# atmega_embedded_main_-_za_drugog_Marka.net
KiCad netlist of a schematic drawn in EAGLE
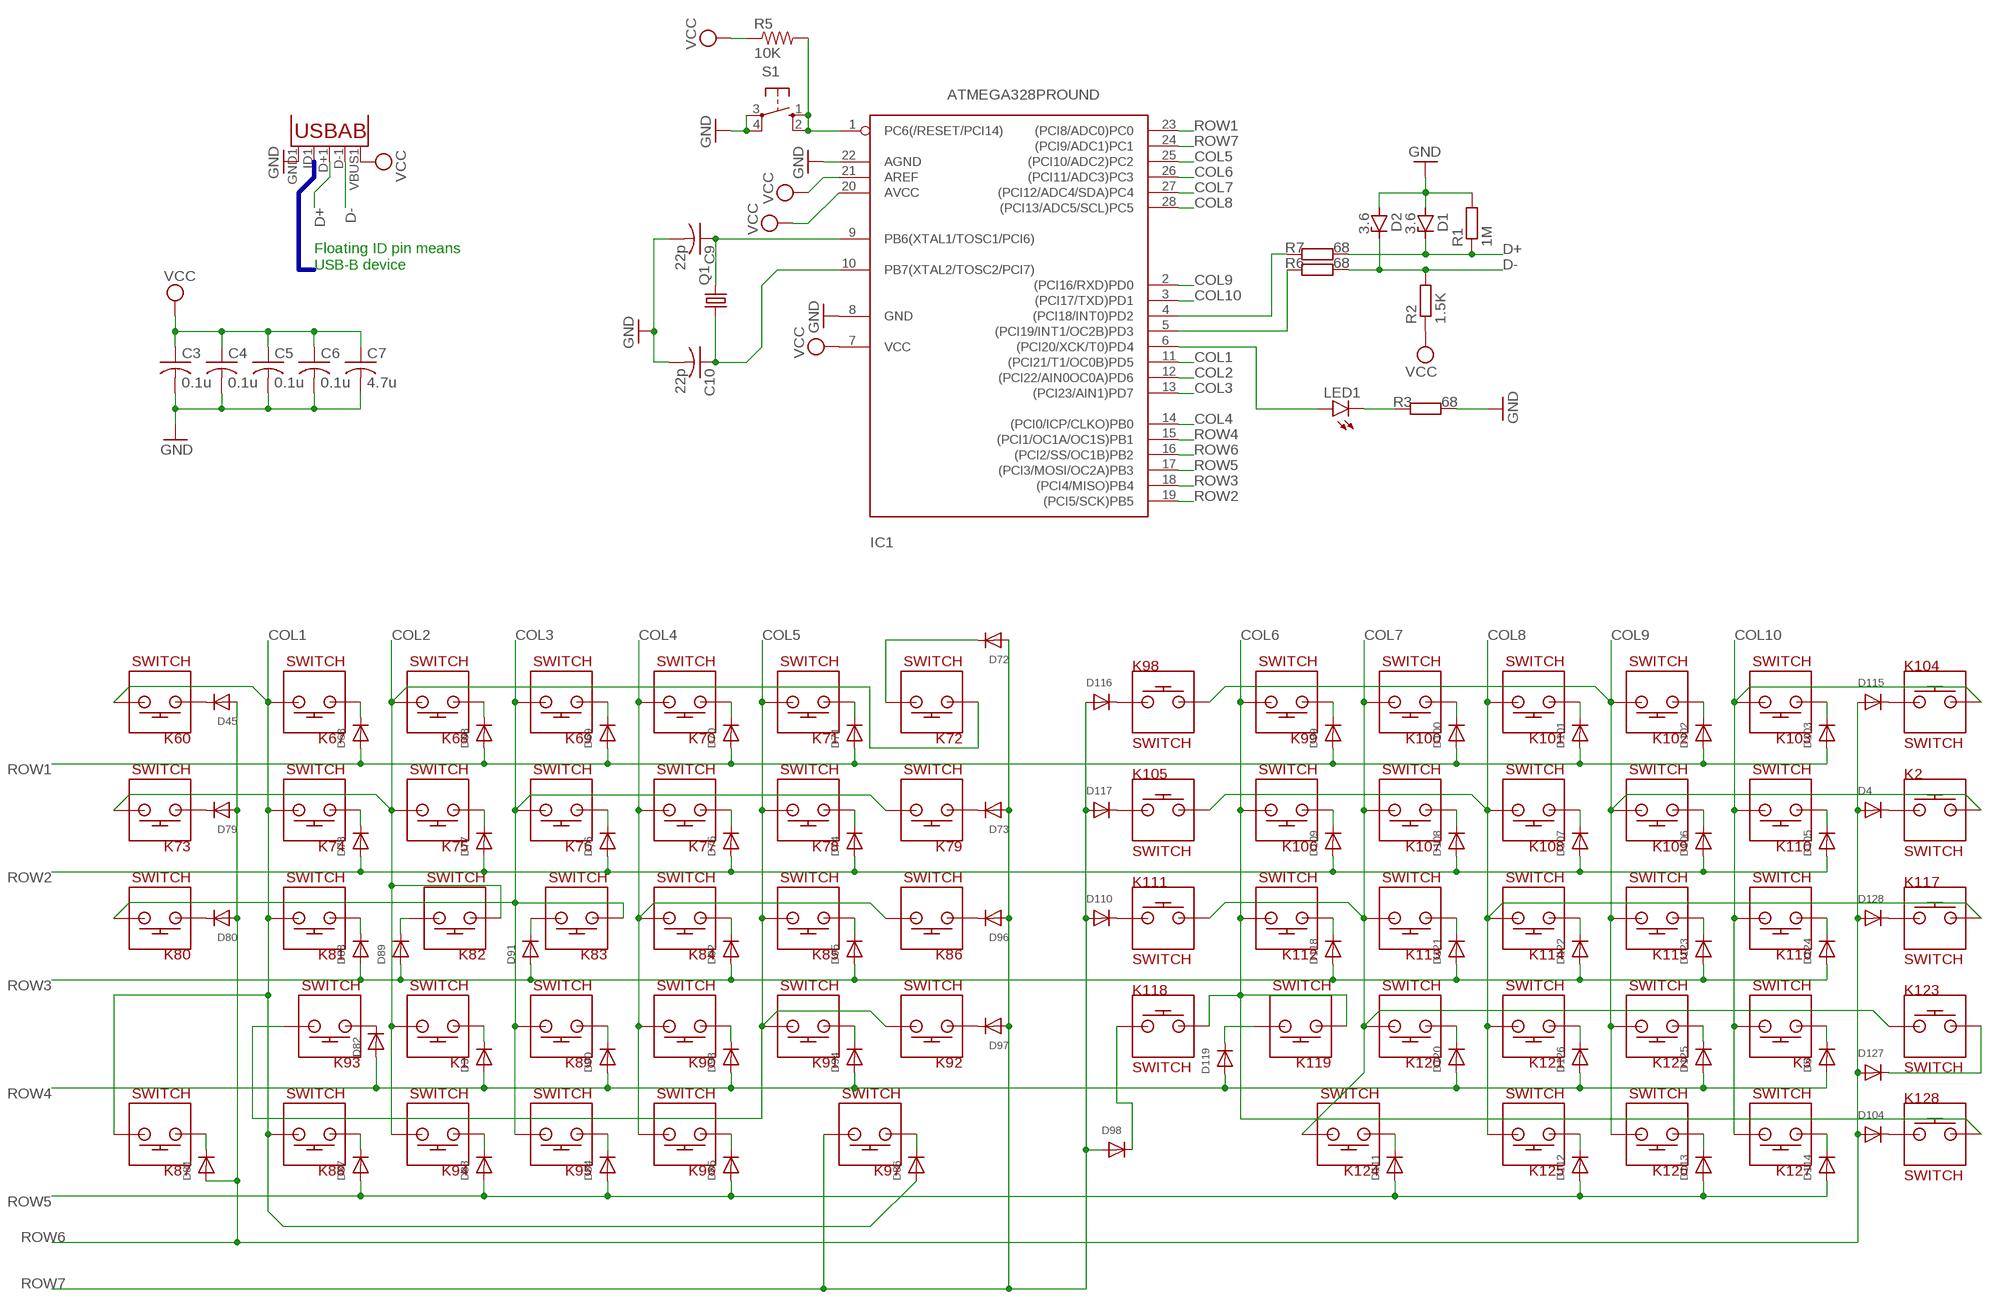
[diagram p0: schematic, sheet 1]

(export (version "E")
  (design (tool "Eeschema 10.0.6"))
  (components
    (comp (ref "C3")
      (value "0.1u")
      (footprint "eagle-import:C0805")
      (libsource (lib "eagle-import") (part "C-USC0805"))
    )
    (comp (ref "C4")
      (value "0.1u")
      (footprint "eagle-import:C0805")
      (libsource (lib "eagle-import") (part "C-USC0805"))
    )
    (comp (ref "C5")
      (value "0.1u")
      (footprint "eagle-import:C0805")
      (libsource (lib "eagle-import") (part "C-USC0805"))
    )
    (comp (ref "C6")
      (value "0.1u")
      (footprint "eagle-import:C0805")
      (libsource (lib "eagle-import") (part "C-USC0805"))
    )
    (comp (ref "C7")
      (value "4.7u")
      (footprint "eagle-import:C0805")
      (libsource (lib "eagle-import") (part "C-USC0805"))
    )
    (comp (ref "C9")
      (value "22p")
      (footprint "eagle-import:C0805")
      (libsource (lib "eagle-import") (part "C-USC0805"))
    )
    (comp (ref "C10")
      (value "22p")
      (footprint "eagle-import:C0805")
      (libsource (lib "eagle-import") (part "C-USC0805"))
    )
    (comp (ref "D1")
      (value "3.6")
      (footprint "eagle-import:SMB")
      (libsource (lib "eagle-import") (part "ZENER-DIODESMB"))
    )
    (comp (ref "D2")
      (value "3.6")
      (footprint "eagle-import:SMB")
      (libsource (lib "eagle-import") (part "ZENER-DIODESMB"))
    )
    (comp (ref "D3")
      (value "DIODESMA")
      (footprint "eagle-import:SMADIODE")
      (libsource (lib "eagle-import") (part "DIODESMA"))
    )
    (comp (ref "D4")
      (value "DIODESMA")
      (footprint "eagle-import:SMADIODE")
      (libsource (lib "eagle-import") (part "DIODESMA"))
    )
    (comp (ref "D5")
      (value "DIODESMA")
      (footprint "eagle-import:SMADIODE")
      (libsource (lib "eagle-import") (part "DIODESMA"))
    )
    (comp (ref "D45")
      (value "DIODESMA")
      (footprint "eagle-import:SMADIODE")
      (libsource (lib "eagle-import") (part "DIODESMA"))
    )
    (comp (ref "D63")
      (value "DIODESMA")
      (footprint "eagle-import:SMADIODE")
      (libsource (lib "eagle-import") (part "DIODESMA"))
    )
    (comp (ref "D68")
      (value "DIODESMA")
      (footprint "eagle-import:SMADIODE")
      (libsource (lib "eagle-import") (part "DIODESMA"))
    )
    (comp (ref "D69")
      (value "DIODESMA")
      (footprint "eagle-import:SMADIODE")
      (libsource (lib "eagle-import") (part "DIODESMA"))
    )
    (comp (ref "D70")
      (value "DIODESMA")
      (footprint "eagle-import:SMADIODE")
      (libsource (lib "eagle-import") (part "DIODESMA"))
    )
    (comp (ref "D71")
      (value "DIODESMA")
      (footprint "eagle-import:SMADIODE")
      (libsource (lib "eagle-import") (part "DIODESMA"))
    )
    (comp (ref "D72")
      (value "DIODESMA")
      (footprint "eagle-import:SMADIODE")
      (libsource (lib "eagle-import") (part "DIODESMA"))
    )
    (comp (ref "D73")
      (value "DIODESMA")
      (footprint "eagle-import:SMADIODE")
      (libsource (lib "eagle-import") (part "DIODESMA"))
    )
    (comp (ref "D74")
      (value "DIODESMA")
      (footprint "eagle-import:SMADIODE")
      (libsource (lib "eagle-import") (part "DIODESMA"))
    )
    (comp (ref "D75")
      (value "DIODESMA")
      (footprint "eagle-import:SMADIODE")
      (libsource (lib "eagle-import") (part "DIODESMA"))
    )
    (comp (ref "D76")
      (value "DIODESMA")
      (footprint "eagle-import:SMADIODE")
      (libsource (lib "eagle-import") (part "DIODESMA"))
    )
    (comp (ref "D77")
      (value "DIODESMA")
      (footprint "eagle-import:SMADIODE")
      (libsource (lib "eagle-import") (part "DIODESMA"))
    )
    (comp (ref "D78")
      (value "DIODESMA")
      (footprint "eagle-import:SMADIODE")
      (libsource (lib "eagle-import") (part "DIODESMA"))
    )
    (comp (ref "D79")
      (value "DIODESMA")
      (footprint "eagle-import:SMADIODE")
      (libsource (lib "eagle-import") (part "DIODESMA"))
    )
    (comp (ref "D80")
      (value "DIODESMA")
      (footprint "eagle-import:SMADIODE")
      (libsource (lib "eagle-import") (part "DIODESMA"))
    )
    (comp (ref "D81")
      (value "DIODESMA")
      (footprint "eagle-import:SMADIODE")
      (libsource (lib "eagle-import") (part "DIODESMA"))
    )
    (comp (ref "D82")
      (value "DIODESMA")
      (footprint "eagle-import:SMADIODE")
      (libsource (lib "eagle-import") (part "DIODESMA"))
    )
    (comp (ref "D83")
      (value "DIODESMA")
      (footprint "eagle-import:SMADIODE")
      (libsource (lib "eagle-import") (part "DIODESMA"))
    )
    (comp (ref "D84")
      (value "DIODESMA")
      (footprint "eagle-import:SMADIODE")
      (libsource (lib "eagle-import") (part "DIODESMA"))
    )
    (comp (ref "D85")
      (value "DIODESMA")
      (footprint "eagle-import:SMADIODE")
      (libsource (lib "eagle-import") (part "DIODESMA"))
    )
    (comp (ref "D86")
      (value "DIODESMA")
      (footprint "eagle-import:SMADIODE")
      (libsource (lib "eagle-import") (part "DIODESMA"))
    )
    (comp (ref "D87")
      (value "DIODESMA")
      (footprint "eagle-import:SMADIODE")
      (libsource (lib "eagle-import") (part "DIODESMA"))
    )
    (comp (ref "D88")
      (value "DIODESMA")
      (footprint "eagle-import:SMADIODE")
      (libsource (lib "eagle-import") (part "DIODESMA"))
    )
    (comp (ref "D89")
      (value "DIODESMA")
      (footprint "eagle-import:SMADIODE")
      (libsource (lib "eagle-import") (part "DIODESMA"))
    )
    (comp (ref "D90")
      (value "DIODESMA")
      (footprint "eagle-import:SMADIODE")
      (libsource (lib "eagle-import") (part "DIODESMA"))
    )
    (comp (ref "D91")
      (value "DIODESMA")
      (footprint "eagle-import:SMADIODE")
      (libsource (lib "eagle-import") (part "DIODESMA"))
    )
    (comp (ref "D92")
      (value "DIODESMA")
      (footprint "eagle-import:SMADIODE")
      (libsource (lib "eagle-import") (part "DIODESMA"))
    )
    (comp (ref "D93")
      (value "DIODESMA")
      (footprint "eagle-import:SMADIODE")
      (libsource (lib "eagle-import") (part "DIODESMA"))
    )
    (comp (ref "D94")
      (value "DIODESMA")
      (footprint "eagle-import:SMADIODE")
      (libsource (lib "eagle-import") (part "DIODESMA"))
    )
    (comp (ref "D95")
      (value "DIODESMA")
      (footprint "eagle-import:SMADIODE")
      (libsource (lib "eagle-import") (part "DIODESMA"))
    )
    (comp (ref "D96")
      (value "DIODESMA")
      (footprint "eagle-import:SMADIODE")
      (libsource (lib "eagle-import") (part "DIODESMA"))
    )
    (comp (ref "D97")
      (value "DIODESMA")
      (footprint "eagle-import:SMADIODE")
      (libsource (lib "eagle-import") (part "DIODESMA"))
    )
    (comp (ref "D98")
      (value "DIODESMA")
      (footprint "eagle-import:SMADIODE")
      (libsource (lib "eagle-import") (part "DIODESMA"))
    )
    (comp (ref "D99")
      (value "DIODESMA")
      (footprint "eagle-import:SMADIODE")
      (libsource (lib "eagle-import") (part "DIODESMA"))
    )
    (comp (ref "D100")
      (value "DIODESMA")
      (footprint "eagle-import:SMADIODE")
      (libsource (lib "eagle-import") (part "DIODESMA"))
    )
    (comp (ref "D101")
      (value "DIODESMA")
      (footprint "eagle-import:SMADIODE")
      (libsource (lib "eagle-import") (part "DIODESMA"))
    )
    (comp (ref "D102")
      (value "DIODESMA")
      (footprint "eagle-import:SMADIODE")
      (libsource (lib "eagle-import") (part "DIODESMA"))
    )
    (comp (ref "D103")
      (value "DIODESMA")
      (footprint "eagle-import:SMADIODE")
      (libsource (lib "eagle-import") (part "DIODESMA"))
    )
    (comp (ref "D104")
      (value "DIODESMA")
      (footprint "eagle-import:SMADIODE")
      (libsource (lib "eagle-import") (part "DIODESMA"))
    )
    (comp (ref "D105")
      (value "DIODESMA")
      (footprint "eagle-import:SMADIODE")
      (libsource (lib "eagle-import") (part "DIODESMA"))
    )
    (comp (ref "D106")
      (value "DIODESMA")
      (footprint "eagle-import:SMADIODE")
      (libsource (lib "eagle-import") (part "DIODESMA"))
    )
    (comp (ref "D107")
      (value "DIODESMA")
      (footprint "eagle-import:SMADIODE")
      (libsource (lib "eagle-import") (part "DIODESMA"))
    )
    (comp (ref "D108")
      (value "DIODESMA")
      (footprint "eagle-import:SMADIODE")
      (libsource (lib "eagle-import") (part "DIODESMA"))
    )
    (comp (ref "D109")
      (value "DIODESMA")
      (footprint "eagle-import:SMADIODE")
      (libsource (lib "eagle-import") (part "DIODESMA"))
    )
    (comp (ref "D110")
      (value "DIODESMA")
      (footprint "eagle-import:SMADIODE")
      (libsource (lib "eagle-import") (part "DIODESMA"))
    )
    (comp (ref "D111")
      (value "DIODESMA")
      (footprint "eagle-import:SMADIODE")
      (libsource (lib "eagle-import") (part "DIODESMA"))
    )
    (comp (ref "D112")
      (value "DIODESMA")
      (footprint "eagle-import:SMADIODE")
      (libsource (lib "eagle-import") (part "DIODESMA"))
    )
    (comp (ref "D113")
      (value "DIODESMA")
      (footprint "eagle-import:SMADIODE")
      (libsource (lib "eagle-import") (part "DIODESMA"))
    )
    (comp (ref "D114")
      (value "DIODESMA")
      (footprint "eagle-import:SMADIODE")
      (libsource (lib "eagle-import") (part "DIODESMA"))
    )
    (comp (ref "D115")
      (value "DIODESMA")
      (footprint "eagle-import:SMADIODE")
      (libsource (lib "eagle-import") (part "DIODESMA"))
    )
    (comp (ref "D116")
      (value "DIODESMA")
      (footprint "eagle-import:SMADIODE")
      (libsource (lib "eagle-import") (part "DIODESMA"))
    )
    (comp (ref "D117")
      (value "DIODESMA")
      (footprint "eagle-import:SMADIODE")
      (libsource (lib "eagle-import") (part "DIODESMA"))
    )
    (comp (ref "D118")
      (value "DIODESMA")
      (footprint "eagle-import:SMADIODE")
      (libsource (lib "eagle-import") (part "DIODESMA"))
    )
    (comp (ref "D119")
      (value "DIODESMA")
      (footprint "eagle-import:SMADIODE")
      (libsource (lib "eagle-import") (part "DIODESMA"))
    )
    (comp (ref "D120")
      (value "DIODESMA")
      (footprint "eagle-import:SMADIODE")
      (libsource (lib "eagle-import") (part "DIODESMA"))
    )
    (comp (ref "D121")
      (value "DIODESMA")
      (footprint "eagle-import:SMADIODE")
      (libsource (lib "eagle-import") (part "DIODESMA"))
    )
    (comp (ref "D122")
      (value "DIODESMA")
      (footprint "eagle-import:SMADIODE")
      (libsource (lib "eagle-import") (part "DIODESMA"))
    )
    (comp (ref "D123")
      (value "DIODESMA")
      (footprint "eagle-import:SMADIODE")
      (libsource (lib "eagle-import") (part "DIODESMA"))
    )
    (comp (ref "D124")
      (value "DIODESMA")
      (footprint "eagle-import:SMADIODE")
      (libsource (lib "eagle-import") (part "DIODESMA"))
    )
    (comp (ref "D125")
      (value "DIODESMA")
      (footprint "eagle-import:SMADIODE")
      (libsource (lib "eagle-import") (part "DIODESMA"))
    )
    (comp (ref "D126")
      (value "DIODESMA")
      (footprint "eagle-import:SMADIODE")
      (libsource (lib "eagle-import") (part "DIODESMA"))
    )
    (comp (ref "D127")
      (value "DIODESMA")
      (footprint "eagle-import:SMADIODE")
      (libsource (lib "eagle-import") (part "DIODESMA"))
    )
    (comp (ref "D128")
      (value "DIODESMA")
      (footprint "eagle-import:SMADIODE")
      (libsource (lib "eagle-import") (part "DIODESMA"))
    )
    (comp (ref "IC1")
      (value "ATMEGA328PROUND")
      (footprint "eagle-import:DIL28-3-ROUND")
      (libsource (lib "eagle-import") (part "ATMEGA328PROUND"))
    )
    (comp (ref "K1")
      (value "SWITCH")
      (footprint "eagle-import:KAILH_LOW_PROFILE")
      (libsource (lib "eagle-import") (part "SWITCH"))
    )
    (comp (ref "K2")
      (value "SWITCH")
      (footprint "eagle-import:KAILH_LOW_PROFILE")
      (libsource (lib "eagle-import") (part "SWITCH"))
    )
    (comp (ref "K3")
      (value "SWITCH")
      (footprint "eagle-import:KAILH_LOW_PROFILE")
      (libsource (lib "eagle-import") (part "SWITCH"))
    )
    (comp (ref "K60")
      (value "SWITCH")
      (footprint "eagle-import:KAILH_LOW_PROFILE")
      (libsource (lib "eagle-import") (part "SWITCH"))
    )
    (comp (ref "K67")
      (value "SWITCH")
      (footprint "eagle-import:KAILH_LOW_PROFILE")
      (libsource (lib "eagle-import") (part "SWITCH"))
    )
    (comp (ref "K68")
      (value "SWITCH")
      (footprint "eagle-import:KAILH_LOW_PROFILE")
      (libsource (lib "eagle-import") (part "SWITCH"))
    )
    (comp (ref "K69")
      (value "SWITCH")
      (footprint "eagle-import:KAILH_LOW_PROFILE")
      (libsource (lib "eagle-import") (part "SWITCH"))
    )
    (comp (ref "K70")
      (value "SWITCH")
      (footprint "eagle-import:KAILH_LOW_PROFILE")
      (libsource (lib "eagle-import") (part "SWITCH"))
    )
    (comp (ref "K71")
      (value "SWITCH")
      (footprint "eagle-import:KAILH_LOW_PROFILE")
      (libsource (lib "eagle-import") (part "SWITCH"))
    )
    (comp (ref "K72")
      (value "SWITCH")
      (footprint "eagle-import:KAILH_LOW_PROFILE")
      (libsource (lib "eagle-import") (part "SWITCH"))
    )
    (comp (ref "K73")
      (value "SWITCH")
      (footprint "eagle-import:KAILH_LOW_PROFILE")
      (libsource (lib "eagle-import") (part "SWITCH"))
    )
    (comp (ref "K74")
      (value "SWITCH")
      (footprint "eagle-import:KAILH_LOW_PROFILE")
      (libsource (lib "eagle-import") (part "SWITCH"))
    )
    (comp (ref "K75")
      (value "SWITCH")
      (footprint "eagle-import:KAILH_LOW_PROFILE")
      (libsource (lib "eagle-import") (part "SWITCH"))
    )
    (comp (ref "K76")
      (value "SWITCH")
      (footprint "eagle-import:KAILH_LOW_PROFILE")
      (libsource (lib "eagle-import") (part "SWITCH"))
    )
    (comp (ref "K77")
      (value "SWITCH")
      (footprint "eagle-import:KAILH_LOW_PROFILE")
      (libsource (lib "eagle-import") (part "SWITCH"))
    )
    (comp (ref "K78")
      (value "SWITCH")
      (footprint "eagle-import:KAILH_LOW_PROFILE")
      (libsource (lib "eagle-import") (part "SWITCH"))
    )
    (comp (ref "K79")
      (value "SWITCH")
      (footprint "eagle-import:KAILH_LOW_PROFILE")
      (libsource (lib "eagle-import") (part "SWITCH"))
    )
    (comp (ref "K80")
      (value "SWITCH")
      (footprint "eagle-import:KAILH_LOW_PROFILE")
      (libsource (lib "eagle-import") (part "SWITCH"))
    )
    (comp (ref "K81")
      (value "SWITCH")
      (footprint "eagle-import:KAILH_LOW_PROFILE")
      (libsource (lib "eagle-import") (part "SWITCH"))
    )
    (comp (ref "K82")
      (value "SWITCH")
      (footprint "eagle-import:KAILH_LOW_PROFILE")
      (libsource (lib "eagle-import") (part "SWITCH"))
    )
    (comp (ref "K83")
      (value "SWITCH")
      (footprint "eagle-import:KAILH_LOW_PROFILE")
      (libsource (lib "eagle-import") (part "SWITCH"))
    )
    (comp (ref "K84")
      (value "SWITCH")
      (footprint "eagle-import:KAILH_LOW_PROFILE")
      (libsource (lib "eagle-import") (part "SWITCH"))
    )
    (comp (ref "K85")
      (value "SWITCH")
      (footprint "eagle-import:KAILH_LOW_PROFILE")
      (libsource (lib "eagle-import") (part "SWITCH"))
    )
    (comp (ref "K86")
      (value "SWITCH")
      (footprint "eagle-import:KAILH_LOW_PROFILE")
      (libsource (lib "eagle-import") (part "SWITCH"))
    )
    (comp (ref "K87")
      (value "SWITCH")
      (footprint "eagle-import:KAILH_LOW_PROFILE")
      (libsource (lib "eagle-import") (part "SWITCH"))
    )
    (comp (ref "K88")
      (value "SWITCH")
      (footprint "eagle-import:KAILH_LOW_PROFILE")
      (libsource (lib "eagle-import") (part "SWITCH"))
    )
    (comp (ref "K89")
      (value "SWITCH")
      (footprint "eagle-import:KAILH_LOW_PROFILE")
      (libsource (lib "eagle-import") (part "SWITCH"))
    )
    (comp (ref "K90")
      (value "SWITCH")
      (footprint "eagle-import:KAILH_LOW_PROFILE")
      (libsource (lib "eagle-import") (part "SWITCH"))
    )
    (comp (ref "K91")
      (value "SWITCH")
      (footprint "eagle-import:KAILH_LOW_PROFILE")
      (libsource (lib "eagle-import") (part "SWITCH"))
    )
    (comp (ref "K92")
      (value "SWITCH")
      (footprint "eagle-import:KAILH_LOW_PROFILE")
      (libsource (lib "eagle-import") (part "SWITCH"))
    )
    (comp (ref "K93")
      (value "SWITCH")
      (footprint "eagle-import:KAILH_LOW_PROFILE")
      (libsource (lib "eagle-import") (part "SWITCH"))
    )
    (comp (ref "K94")
      (value "SWITCH")
      (footprint "eagle-import:KAILH_LOW_PROFILE")
      (libsource (lib "eagle-import") (part "SWITCH"))
    )
    (comp (ref "K95")
      (value "SWITCH")
      (footprint "eagle-import:KAILH_LOW_PROFILE")
      (libsource (lib "eagle-import") (part "SWITCH"))
    )
    (comp (ref "K96")
      (value "SWITCH")
      (footprint "eagle-import:KAILH_LOW_PROFILE")
      (libsource (lib "eagle-import") (part "SWITCH"))
    )
    (comp (ref "K97")
      (value "SWITCH")
      (footprint "eagle-import:KAILH_LOW_PROFILE")
      (libsource (lib "eagle-import") (part "SWITCH"))
    )
    (comp (ref "K98")
      (value "SWITCH")
      (footprint "eagle-import:KAILH_LOW_PROFILE")
      (libsource (lib "eagle-import") (part "SWITCH"))
    )
    (comp (ref "K99")
      (value "SWITCH")
      (footprint "eagle-import:KAILH_LOW_PROFILE")
      (libsource (lib "eagle-import") (part "SWITCH"))
    )
    (comp (ref "K100")
      (value "SWITCH")
      (footprint "eagle-import:KAILH_LOW_PROFILE")
      (libsource (lib "eagle-import") (part "SWITCH"))
    )
    (comp (ref "K101")
      (value "SWITCH")
      (footprint "eagle-import:KAILH_LOW_PROFILE")
      (libsource (lib "eagle-import") (part "SWITCH"))
    )
    (comp (ref "K102")
      (value "SWITCH")
      (footprint "eagle-import:KAILH_LOW_PROFILE")
      (libsource (lib "eagle-import") (part "SWITCH"))
    )
    (comp (ref "K103")
      (value "SWITCH")
      (footprint "eagle-import:KAILH_LOW_PROFILE")
      (libsource (lib "eagle-import") (part "SWITCH"))
    )
    (comp (ref "K104")
      (value "SWITCH")
      (footprint "eagle-import:KAILH_LOW_PROFILE")
      (libsource (lib "eagle-import") (part "SWITCH"))
    )
    (comp (ref "K105")
      (value "SWITCH")
      (footprint "eagle-import:KAILH_LOW_PROFILE")
      (libsource (lib "eagle-import") (part "SWITCH"))
    )
    (comp (ref "K106")
      (value "SWITCH")
      (footprint "eagle-import:KAILH_LOW_PROFILE")
      (libsource (lib "eagle-import") (part "SWITCH"))
    )
    (comp (ref "K107")
      (value "SWITCH")
      (footprint "eagle-import:KAILH_LOW_PROFILE")
      (libsource (lib "eagle-import") (part "SWITCH"))
    )
    (comp (ref "K108")
      (value "SWITCH")
      (footprint "eagle-import:KAILH_LOW_PROFILE")
      (libsource (lib "eagle-import") (part "SWITCH"))
    )
    (comp (ref "K109")
      (value "SWITCH")
      (footprint "eagle-import:KAILH_LOW_PROFILE")
      (libsource (lib "eagle-import") (part "SWITCH"))
    )
    (comp (ref "K110")
      (value "SWITCH")
      (footprint "eagle-import:KAILH_LOW_PROFILE")
      (libsource (lib "eagle-import") (part "SWITCH"))
    )
    (comp (ref "K111")
      (value "SWITCH")
      (footprint "eagle-import:KAILH_LOW_PROFILE")
      (libsource (lib "eagle-import") (part "SWITCH"))
    )
    (comp (ref "K112")
      (value "SWITCH")
      (footprint "eagle-import:KAILH_LOW_PROFILE")
      (libsource (lib "eagle-import") (part "SWITCH"))
    )
    (comp (ref "K113")
      (value "SWITCH")
      (footprint "eagle-import:KAILH_LOW_PROFILE")
      (libsource (lib "eagle-import") (part "SWITCH"))
    )
    (comp (ref "K114")
      (value "SWITCH")
      (footprint "eagle-import:KAILH_LOW_PROFILE")
      (libsource (lib "eagle-import") (part "SWITCH"))
    )
    (comp (ref "K115")
      (value "SWITCH")
      (footprint "eagle-import:KAILH_LOW_PROFILE")
      (libsource (lib "eagle-import") (part "SWITCH"))
    )
    (comp (ref "K116")
      (value "SWITCH")
      (footprint "eagle-import:KAILH_LOW_PROFILE")
      (libsource (lib "eagle-import") (part "SWITCH"))
    )
    (comp (ref "K117")
      (value "SWITCH")
      (footprint "eagle-import:KAILH_LOW_PROFILE")
      (libsource (lib "eagle-import") (part "SWITCH"))
    )
    (comp (ref "K118")
      (value "SWITCH")
      (footprint "eagle-import:KAILH_LOW_PROFILE")
      (libsource (lib "eagle-import") (part "SWITCH"))
    )
    (comp (ref "K119")
      (value "SWITCH")
      (footprint "eagle-import:KAILH_LOW_PROFILE")
      (libsource (lib "eagle-import") (part "SWITCH"))
    )
    (comp (ref "K120")
      (value "SWITCH")
      (footprint "eagle-import:KAILH_LOW_PROFILE")
      (libsource (lib "eagle-import") (part "SWITCH"))
    )
    (comp (ref "K121")
      (value "SWITCH")
      (footprint "eagle-import:KAILH_LOW_PROFILE")
      (libsource (lib "eagle-import") (part "SWITCH"))
    )
    (comp (ref "K122")
      (value "SWITCH")
      (footprint "eagle-import:KAILH_LOW_PROFILE")
      (libsource (lib "eagle-import") (part "SWITCH"))
    )
    (comp (ref "K123")
      (value "SWITCH")
      (footprint "eagle-import:KAILH_LOW_PROFILE")
      (libsource (lib "eagle-import") (part "SWITCH"))
    )
    (comp (ref "K124")
      (value "SWITCH")
      (footprint "eagle-import:KAILH_LOW_PROFILE")
      (libsource (lib "eagle-import") (part "SWITCH"))
    )
    (comp (ref "K125")
      (value "SWITCH")
      (footprint "eagle-import:KAILH_LOW_PROFILE")
      (libsource (lib "eagle-import") (part "SWITCH"))
    )
    (comp (ref "K126")
      (value "SWITCH")
      (footprint "eagle-import:KAILH_LOW_PROFILE")
      (libsource (lib "eagle-import") (part "SWITCH"))
    )
    (comp (ref "K127")
      (value "SWITCH")
      (footprint "eagle-import:KAILH_LOW_PROFILE")
      (libsource (lib "eagle-import") (part "SWITCH"))
    )
    (comp (ref "K128")
      (value "SWITCH")
      (footprint "eagle-import:KAILH_LOW_PROFILE")
      (libsource (lib "eagle-import") (part "SWITCH"))
    )
    (comp (ref "LED1")
      (value "LEDCHIPLED_1206")
      (footprint "eagle-import:CHIPLED_1206")
      (libsource (lib "eagle-import") (part "LEDCHIPLED_1206"))
    )
    (comp (ref "Q1")
      (value "CRYSTALHC49S")
      (footprint "eagle-import:HC49_S")
      (libsource (lib "eagle-import") (part "CRYSTALHC49S"))
    )
    (comp (ref "R1")
      (value "1M")
      (footprint "eagle-import:R1206")
      (libsource (lib "eagle-import") (part "RR1206"))
    )
    (comp (ref "R2")
      (value "1.5K")
      (footprint "eagle-import:R1206")
      (libsource (lib "eagle-import") (part "RR1206"))
    )
    (comp (ref "R3")
      (value "68")
      (footprint "eagle-import:R1206")
      (libsource (lib "eagle-import") (part "RR1206"))
    )
    (comp (ref "R5")
      (value "10K")
      (footprint "eagle-import:M0805")
      (libsource (lib "eagle-import") (part "R-US_M0805"))
    )
    (comp (ref "R6")
      (value "68")
      (footprint "eagle-import:R1206")
      (libsource (lib "eagle-import") (part "RR1206"))
    )
    (comp (ref "R7")
      (value "68")
      (footprint "eagle-import:R1206")
      (libsource (lib "eagle-import") (part "RR1206"))
    )
    (comp (ref "S1")
      (value "10-XX")
      (footprint "eagle-import:B3F-10XX")
      (fields (field (name "MPN") "B3F-1000"))
      (libsource (lib "eagle-import") (part "10-XX"))
    )
    (comp (ref "U1")
      (value "USB\"\"")
      (footprint "eagle-import:USB-MICRO-SMD")
      (libsource (lib "eagle-import") (part "USB{dblquote}{dblquote}"))
    )
  )
  (nets
    (net (code "1") (name "/COL1") (class "Default")
      (node (ref "D86") (pin "A") (pinfunction "A_A") (pintype "passive"))
      (node (ref "IC1") (pin "11") (pinfunction "(PCI21/T1/OC0B)PD5_11") (pintype "bidirectional"))
      (node (ref "K60") (pin "P$2") (pinfunction "P$2_P$2") (pintype "bidirectional"))
      (node (ref "K67") (pin "P$2") (pinfunction "P$2_P$2") (pintype "bidirectional"))
      (node (ref "K74") (pin "P$2") (pinfunction "P$2_P$2") (pintype "bidirectional"))
      (node (ref "K81") (pin "P$2") (pinfunction "P$2_P$2") (pintype "bidirectional"))
      (node (ref "K87") (pin "P$2") (pinfunction "P$2_P$2") (pintype "bidirectional"))
      (node (ref "K88") (pin "P$2") (pinfunction "P$2_P$2") (pintype "bidirectional"))
    )
    (net (code "2") (name "/COL2") (class "Default")
      (node (ref "IC1") (pin "12") (pinfunction "(PCI22/AIN0OC0A)PD6_12") (pintype "bidirectional"))
      (node (ref "K1") (pin "P$2") (pinfunction "P$2_P$2") (pintype "bidirectional"))
      (node (ref "K68") (pin "P$2") (pinfunction "P$2_P$2") (pintype "bidirectional"))
      (node (ref "K72") (pin "P$1") (pinfunction "P$1_P$1") (pintype "bidirectional"))
      (node (ref "K73") (pin "P$2") (pinfunction "P$2_P$2") (pintype "bidirectional"))
      (node (ref "K75") (pin "P$2") (pinfunction "P$2_P$2") (pintype "bidirectional"))
      (node (ref "K82") (pin "P$1") (pinfunction "P$1_P$1") (pintype "bidirectional"))
      (node (ref "K94") (pin "P$2") (pinfunction "P$2_P$2") (pintype "bidirectional"))
    )
    (net (code "3") (name "/COL3") (class "Default")
      (node (ref "IC1") (pin "13") (pinfunction "(PCI23/AIN1)PD7_13") (pintype "bidirectional"))
      (node (ref "K69") (pin "P$2") (pinfunction "P$2_P$2") (pintype "bidirectional"))
      (node (ref "K76") (pin "P$2") (pinfunction "P$2_P$2") (pintype "bidirectional"))
      (node (ref "K79") (pin "P$2") (pinfunction "P$2_P$2") (pintype "bidirectional"))
      (node (ref "K80") (pin "P$2") (pinfunction "P$2_P$2") (pintype "bidirectional"))
      (node (ref "K83") (pin "P$1") (pinfunction "P$1_P$1") (pintype "bidirectional"))
      (node (ref "K89") (pin "P$2") (pinfunction "P$2_P$2") (pintype "bidirectional"))
      (node (ref "K95") (pin "P$2") (pinfunction "P$2_P$2") (pintype "bidirectional"))
    )
    (net (code "4") (name "/COL4") (class "Default")
      (node (ref "IC1") (pin "14") (pinfunction "(PCI0/ICP/CLKO)PB0_14") (pintype "bidirectional"))
      (node (ref "K70") (pin "P$2") (pinfunction "P$2_P$2") (pintype "bidirectional"))
      (node (ref "K77") (pin "P$2") (pinfunction "P$2_P$2") (pintype "bidirectional"))
      (node (ref "K84") (pin "P$2") (pinfunction "P$2_P$2") (pintype "bidirectional"))
      (node (ref "K86") (pin "P$2") (pinfunction "P$2_P$2") (pintype "bidirectional"))
      (node (ref "K90") (pin "P$2") (pinfunction "P$2_P$2") (pintype "bidirectional"))
      (node (ref "K96") (pin "P$2") (pinfunction "P$2_P$2") (pintype "bidirectional"))
    )
    (net (code "5") (name "/COL5") (class "Default")
      (node (ref "IC1") (pin "25") (pinfunction "(PCI10/ADC2)PC2_25") (pintype "bidirectional"))
      (node (ref "K71") (pin "P$2") (pinfunction "P$2_P$2") (pintype "bidirectional"))
      (node (ref "K78") (pin "P$2") (pinfunction "P$2_P$2") (pintype "bidirectional"))
      (node (ref "K85") (pin "P$2") (pinfunction "P$2_P$2") (pintype "bidirectional"))
      (node (ref "K91") (pin "P$2") (pinfunction "P$2_P$2") (pintype "bidirectional"))
      (node (ref "K92") (pin "P$2") (pinfunction "P$2_P$2") (pintype "bidirectional"))
      (node (ref "K93") (pin "P$2") (pinfunction "P$2_P$2") (pintype "bidirectional"))
    )
    (net (code "6") (name "/COL6") (class "Default")
      (node (ref "IC1") (pin "26") (pinfunction "(PCI11/ADC3)PC3_26") (pintype "bidirectional"))
      (node (ref "K106") (pin "P$2") (pinfunction "P$2_P$2") (pintype "bidirectional"))
      (node (ref "K112") (pin "P$2") (pinfunction "P$2_P$2") (pintype "bidirectional"))
      (node (ref "K118") (pin "P$2") (pinfunction "P$2_P$2") (pintype "bidirectional"))
      (node (ref "K119") (pin "P$1") (pinfunction "P$1_P$1") (pintype "bidirectional"))
      (node (ref "K128") (pin "P$2") (pinfunction "P$2_P$2") (pintype "bidirectional"))
      (node (ref "K99") (pin "P$2") (pinfunction "P$2_P$2") (pintype "bidirectional"))
    )
    (net (code "7") (name "/COL7") (class "Default")
      (node (ref "IC1") (pin "27") (pinfunction "(PCI12/ADC4/SDA)PC4_27") (pintype "bidirectional"))
      (node (ref "K100") (pin "P$2") (pinfunction "P$2_P$2") (pintype "bidirectional"))
      (node (ref "K107") (pin "P$2") (pinfunction "P$2_P$2") (pintype "bidirectional"))
      (node (ref "K111") (pin "P$2") (pinfunction "P$2_P$2") (pintype "bidirectional"))
      (node (ref "K113") (pin "P$2") (pinfunction "P$2_P$2") (pintype "bidirectional"))
      (node (ref "K120") (pin "P$2") (pinfunction "P$2_P$2") (pintype "bidirectional"))
      (node (ref "K123") (pin "P$1") (pinfunction "P$1_P$1") (pintype "bidirectional"))
      (node (ref "K124") (pin "P$2") (pinfunction "P$2_P$2") (pintype "bidirectional"))
    )
    (net (code "8") (name "/COL8") (class "Default")
      (node (ref "IC1") (pin "28") (pinfunction "(PCI13/ADC5/SCL)PC5_28") (pintype "bidirectional"))
      (node (ref "K101") (pin "P$2") (pinfunction "P$2_P$2") (pintype "bidirectional"))
      (node (ref "K105") (pin "P$2") (pinfunction "P$2_P$2") (pintype "bidirectional"))
      (node (ref "K108") (pin "P$2") (pinfunction "P$2_P$2") (pintype "bidirectional"))
      (node (ref "K114") (pin "P$2") (pinfunction "P$2_P$2") (pintype "bidirectional"))
      (node (ref "K117") (pin "P$2") (pinfunction "P$2_P$2") (pintype "bidirectional"))
      (node (ref "K121") (pin "P$2") (pinfunction "P$2_P$2") (pintype "bidirectional"))
      (node (ref "K125") (pin "P$2") (pinfunction "P$2_P$2") (pintype "bidirectional"))
    )
    (net (code "9") (name "/COL9") (class "Default")
      (node (ref "IC1") (pin "2") (pinfunction "(PCI16/RXD)PD0_2") (pintype "bidirectional"))
      (node (ref "K102") (pin "P$2") (pinfunction "P$2_P$2") (pintype "bidirectional"))
      (node (ref "K109") (pin "P$2") (pinfunction "P$2_P$2") (pintype "bidirectional"))
      (node (ref "K115") (pin "P$2") (pinfunction "P$2_P$2") (pintype "bidirectional"))
      (node (ref "K122") (pin "P$2") (pinfunction "P$2_P$2") (pintype "bidirectional"))
      (node (ref "K126") (pin "P$2") (pinfunction "P$2_P$2") (pintype "bidirectional"))
      (node (ref "K2") (pin "P$2") (pinfunction "P$2_P$2") (pintype "bidirectional"))
      (node (ref "K98") (pin "P$2") (pinfunction "P$2_P$2") (pintype "bidirectional"))
    )
    (net (code "10") (name "/COL10") (class "Default")
      (node (ref "IC1") (pin "3") (pinfunction "(PCI17/TXD)PD1_3") (pintype "bidirectional"))
      (node (ref "K103") (pin "P$2") (pinfunction "P$2_P$2") (pintype "bidirectional"))
      (node (ref "K104") (pin "P$2") (pinfunction "P$2_P$2") (pintype "bidirectional"))
      (node (ref "K110") (pin "P$2") (pinfunction "P$2_P$2") (pintype "bidirectional"))
      (node (ref "K116") (pin "P$2") (pinfunction "P$2_P$2") (pintype "bidirectional"))
      (node (ref "K127") (pin "P$2") (pinfunction "P$2_P$2") (pintype "bidirectional"))
      (node (ref "K3") (pin "P$2") (pinfunction "P$2_P$2") (pintype "bidirectional"))
    )
    (net (code "11") (name "/D+") (class "Default")
      (node (ref "D1") (pin "C") (pinfunction "C_C") (pintype "passive"))
      (node (ref "R1") (pin "1") (pinfunction "1_1") (pintype "passive"))
      (node (ref "R7") (pin "2") (pinfunction "2_2") (pintype "passive"))
      (node (ref "U1") (pin "D+1") (pinfunction "D+_D+1") (pintype "bidirectional"))
    )
    (net (code "12") (name "/D-") (class "Default")
      (node (ref "D2") (pin "C") (pinfunction "C_C") (pintype "passive"))
      (node (ref "R2") (pin "2") (pinfunction "2_2") (pintype "passive"))
      (node (ref "R6") (pin "2") (pinfunction "2_2") (pintype "passive"))
      (node (ref "U1") (pin "D-1") (pinfunction "D-_D-1") (pintype "bidirectional"))
    )
    (net (code "13") (name "/ROW1") (class "Default")
      (node (ref "D100") (pin "A") (pinfunction "A_A") (pintype "passive"))
      (node (ref "D101") (pin "A") (pinfunction "A_A") (pintype "passive"))
      (node (ref "D102") (pin "A") (pinfunction "A_A") (pintype "passive"))
      (node (ref "D103") (pin "A") (pinfunction "A_A") (pintype "passive"))
      (node (ref "D63") (pin "A") (pinfunction "A_A") (pintype "passive"))
      (node (ref "D68") (pin "A") (pinfunction "A_A") (pintype "passive"))
      (node (ref "D69") (pin "A") (pinfunction "A_A") (pintype "passive"))
      (node (ref "D70") (pin "A") (pinfunction "A_A") (pintype "passive"))
      (node (ref "D71") (pin "A") (pinfunction "A_A") (pintype "passive"))
      (node (ref "D99") (pin "A") (pinfunction "A_A") (pintype "passive"))
      (node (ref "IC1") (pin "23") (pinfunction "(PCI8/ADC0)PC0_23") (pintype "bidirectional"))
    )
    (net (code "14") (name "/ROW2") (class "Default")
      (node (ref "D105") (pin "A") (pinfunction "A_A") (pintype "passive"))
      (node (ref "D106") (pin "A") (pinfunction "A_A") (pintype "passive"))
      (node (ref "D107") (pin "A") (pinfunction "A_A") (pintype "passive"))
      (node (ref "D108") (pin "A") (pinfunction "A_A") (pintype "passive"))
      (node (ref "D109") (pin "A") (pinfunction "A_A") (pintype "passive"))
      (node (ref "D74") (pin "A") (pinfunction "A_A") (pintype "passive"))
      (node (ref "D75") (pin "A") (pinfunction "A_A") (pintype "passive"))
      (node (ref "D76") (pin "A") (pinfunction "A_A") (pintype "passive"))
      (node (ref "D77") (pin "A") (pinfunction "A_A") (pintype "passive"))
      (node (ref "D78") (pin "A") (pinfunction "A_A") (pintype "passive"))
      (node (ref "IC1") (pin "19") (pinfunction "(PCI5/SCK)PB5_19") (pintype "bidirectional"))
    )
    (net (code "15") (name "/ROW3") (class "Default")
      (node (ref "D118") (pin "A") (pinfunction "A_A") (pintype "passive"))
      (node (ref "D121") (pin "A") (pinfunction "A_A") (pintype "passive"))
      (node (ref "D122") (pin "A") (pinfunction "A_A") (pintype "passive"))
      (node (ref "D123") (pin "A") (pinfunction "A_A") (pintype "passive"))
      (node (ref "D124") (pin "A") (pinfunction "A_A") (pintype "passive"))
      (node (ref "D88") (pin "A") (pinfunction "A_A") (pintype "passive"))
      (node (ref "D89") (pin "A") (pinfunction "A_A") (pintype "passive"))
      (node (ref "D91") (pin "A") (pinfunction "A_A") (pintype "passive"))
      (node (ref "D92") (pin "A") (pinfunction "A_A") (pintype "passive"))
      (node (ref "D95") (pin "A") (pinfunction "A_A") (pintype "passive"))
      (node (ref "IC1") (pin "18") (pinfunction "(PCI4/MISO)PB4_18") (pintype "bidirectional"))
    )
    (net (code "16") (name "/ROW4") (class "Default")
      (node (ref "D119") (pin "A") (pinfunction "A_A") (pintype "passive"))
      (node (ref "D120") (pin "A") (pinfunction "A_A") (pintype "passive"))
      (node (ref "D125") (pin "A") (pinfunction "A_A") (pintype "passive"))
      (node (ref "D126") (pin "A") (pinfunction "A_A") (pintype "passive"))
      (node (ref "D3") (pin "A") (pinfunction "A_A") (pintype "passive"))
      (node (ref "D5") (pin "A") (pinfunction "A_A") (pintype "passive"))
      (node (ref "D82") (pin "A") (pinfunction "A_A") (pintype "passive"))
      (node (ref "D90") (pin "A") (pinfunction "A_A") (pintype "passive"))
      (node (ref "D93") (pin "A") (pinfunction "A_A") (pintype "passive"))
      (node (ref "D94") (pin "A") (pinfunction "A_A") (pintype "passive"))
      (node (ref "IC1") (pin "15") (pinfunction "(PCI1/OC1A/OC1S)PB1_15") (pintype "bidirectional"))
    )
    (net (code "17") (name "/ROW5") (class "Default")
      (node (ref "D111") (pin "A") (pinfunction "A_A") (pintype "passive"))
      (node (ref "D112") (pin "A") (pinfunction "A_A") (pintype "passive"))
      (node (ref "D113") (pin "A") (pinfunction "A_A") (pintype "passive"))
      (node (ref "D114") (pin "A") (pinfunction "A_A") (pintype "passive"))
      (node (ref "D83") (pin "A") (pinfunction "A_A") (pintype "passive"))
      (node (ref "D84") (pin "A") (pinfunction "A_A") (pintype "passive"))
      (node (ref "D85") (pin "A") (pinfunction "A_A") (pintype "passive"))
      (node (ref "D87") (pin "A") (pinfunction "A_A") (pintype "passive"))
      (node (ref "IC1") (pin "17") (pinfunction "(PCI3/MOSI/OC2A)PB3_17") (pintype "bidirectional"))
    )
    (net (code "18") (name "/ROW6") (class "Default")
      (node (ref "D104") (pin "A") (pinfunction "A_A") (pintype "passive"))
      (node (ref "D115") (pin "A") (pinfunction "A_A") (pintype "passive"))
      (node (ref "D127") (pin "A") (pinfunction "A_A") (pintype "passive"))
      (node (ref "D128") (pin "A") (pinfunction "A_A") (pintype "passive"))
      (node (ref "D4") (pin "A") (pinfunction "A_A") (pintype "passive"))
      (node (ref "D45") (pin "A") (pinfunction "A_A") (pintype "passive"))
      (node (ref "D79") (pin "A") (pinfunction "A_A") (pintype "passive"))
      (node (ref "D80") (pin "A") (pinfunction "A_A") (pintype "passive"))
      (node (ref "D81") (pin "A") (pinfunction "A_A") (pintype "passive"))
      (node (ref "IC1") (pin "16") (pinfunction "(PCI2/SS/OC1B)PB2_16") (pintype "bidirectional"))
    )
    (net (code "19") (name "/ROW7") (class "Default")
      (node (ref "D110") (pin "A") (pinfunction "A_A") (pintype "passive"))
      (node (ref "D116") (pin "A") (pinfunction "A_A") (pintype "passive"))
      (node (ref "D117") (pin "A") (pinfunction "A_A") (pintype "passive"))
      (node (ref "D72") (pin "A") (pinfunction "A_A") (pintype "passive"))
      (node (ref "D73") (pin "A") (pinfunction "A_A") (pintype "passive"))
      (node (ref "D96") (pin "A") (pinfunction "A_A") (pintype "passive"))
      (node (ref "D97") (pin "A") (pinfunction "A_A") (pintype "passive"))
      (node (ref "D98") (pin "A") (pinfunction "A_A") (pintype "passive"))
      (node (ref "IC1") (pin "24") (pinfunction "(PCI9/ADC1)PC1_24") (pintype "bidirectional"))
      (node (ref "K97") (pin "P$2") (pinfunction "P$2_P$2") (pintype "bidirectional"))
    )
    (net (code "20") (name "GND") (class "Default")
      (node (ref "C10") (pin "2") (pinfunction "2_2") (pintype "passive"))
      (node (ref "C3") (pin "2") (pinfunction "2_2") (pintype "passive"))
      (node (ref "C4") (pin "2") (pinfunction "2_2") (pintype "passive"))
      (node (ref "C5") (pin "2") (pinfunction "2_2") (pintype "passive"))
      (node (ref "C6") (pin "2") (pinfunction "2_2") (pintype "passive"))
      (node (ref "C7") (pin "2") (pinfunction "2_2") (pintype "passive"))
      (node (ref "C9") (pin "2") (pinfunction "2_2") (pintype "passive"))
      (node (ref "D1") (pin "A") (pinfunction "A_A") (pintype "passive"))
      (node (ref "D2") (pin "A") (pinfunction "A_A") (pintype "passive"))
      (node (ref "IC1") (pin "22") (pinfunction "AGND_22") (pintype "bidirectional"))
      (node (ref "IC1") (pin "8") (pinfunction "GND_8") (pintype "bidirectional"))
      (node (ref "R1") (pin "2") (pinfunction "2_2") (pintype "passive"))
      (node (ref "R3") (pin "2") (pinfunction "2_2") (pintype "passive"))
      (node (ref "S1") (pin "3") (pinfunction "P_3") (pintype "passive"))
      (node (ref "S1") (pin "4") (pinfunction "P1_4") (pintype "passive"))
      (node (ref "U1") (pin "GND1") (pinfunction "GND_GND1") (pintype "bidirectional"))
    )
    (net (code "21") (name "Net-(D3-PadC)") (class "Default")
      (node (ref "D3") (pin "C") (pinfunction "C_C") (pintype "passive"))
      (node (ref "K1") (pin "P$1") (pinfunction "P$1_P$1") (pintype "bidirectional"))
    )
    (net (code "22") (name "Net-(D4-PadC)") (class "Default")
      (node (ref "D4") (pin "C") (pinfunction "C_C") (pintype "passive"))
      (node (ref "K2") (pin "P$1") (pinfunction "P$1_P$1") (pintype "bidirectional"))
    )
    (net (code "23") (name "Net-(D5-PadC)") (class "Default")
      (node (ref "D5") (pin "C") (pinfunction "C_C") (pintype "passive"))
      (node (ref "K3") (pin "P$1") (pinfunction "P$1_P$1") (pintype "bidirectional"))
    )
    (net (code "24") (name "Net-(D45-PadC)") (class "Default")
      (node (ref "D45") (pin "C") (pinfunction "C_C") (pintype "passive"))
      (node (ref "K60") (pin "P$1") (pinfunction "P$1_P$1") (pintype "bidirectional"))
    )
    (net (code "25") (name "Net-(D63-PadC)") (class "Default")
      (node (ref "D63") (pin "C") (pinfunction "C_C") (pintype "passive"))
      (node (ref "K67") (pin "P$1") (pinfunction "P$1_P$1") (pintype "bidirectional"))
    )
    (net (code "26") (name "Net-(D68-PadC)") (class "Default")
      (node (ref "D68") (pin "C") (pinfunction "C_C") (pintype "passive"))
      (node (ref "K68") (pin "P$1") (pinfunction "P$1_P$1") (pintype "bidirectional"))
    )
    (net (code "27") (name "Net-(D69-PadC)") (class "Default")
      (node (ref "D69") (pin "C") (pinfunction "C_C") (pintype "passive"))
      (node (ref "K69") (pin "P$1") (pinfunction "P$1_P$1") (pintype "bidirectional"))
    )
    (net (code "28") (name "Net-(D70-PadC)") (class "Default")
      (node (ref "D70") (pin "C") (pinfunction "C_C") (pintype "passive"))
      (node (ref "K70") (pin "P$1") (pinfunction "P$1_P$1") (pintype "bidirectional"))
    )
    (net (code "29") (name "Net-(D71-PadC)") (class "Default")
      (node (ref "D71") (pin "C") (pinfunction "C_C") (pintype "passive"))
      (node (ref "K71") (pin "P$1") (pinfunction "P$1_P$1") (pintype "bidirectional"))
    )
    (net (code "30") (name "Net-(D72-PadC)") (class "Default")
      (node (ref "D72") (pin "C") (pinfunction "C_C") (pintype "passive"))
      (node (ref "K72") (pin "P$2") (pinfunction "P$2_P$2") (pintype "bidirectional"))
    )
    (net (code "31") (name "Net-(D73-PadC)") (class "Default")
      (node (ref "D73") (pin "C") (pinfunction "C_C") (pintype "passive"))
      (node (ref "K79") (pin "P$1") (pinfunction "P$1_P$1") (pintype "bidirectional"))
    )
    (net (code "32") (name "Net-(D74-PadC)") (class "Default")
      (node (ref "D74") (pin "C") (pinfunction "C_C") (pintype "passive"))
      (node (ref "K78") (pin "P$1") (pinfunction "P$1_P$1") (pintype "bidirectional"))
    )
    (net (code "33") (name "Net-(D75-PadC)") (class "Default")
      (node (ref "D75") (pin "C") (pinfunction "C_C") (pintype "passive"))
      (node (ref "K77") (pin "P$1") (pinfunction "P$1_P$1") (pintype "bidirectional"))
    )
    (net (code "34") (name "Net-(D76-PadC)") (class "Default")
      (node (ref "D76") (pin "C") (pinfunction "C_C") (pintype "passive"))
      (node (ref "K76") (pin "P$1") (pinfunction "P$1_P$1") (pintype "bidirectional"))
    )
    (net (code "35") (name "Net-(D77-PadC)") (class "Default")
      (node (ref "D77") (pin "C") (pinfunction "C_C") (pintype "passive"))
      (node (ref "K75") (pin "P$1") (pinfunction "P$1_P$1") (pintype "bidirectional"))
    )
    (net (code "36") (name "Net-(D78-PadC)") (class "Default")
      (node (ref "D78") (pin "C") (pinfunction "C_C") (pintype "passive"))
      (node (ref "K74") (pin "P$1") (pinfunction "P$1_P$1") (pintype "bidirectional"))
    )
    (net (code "37") (name "Net-(D79-PadC)") (class "Default")
      (node (ref "D79") (pin "C") (pinfunction "C_C") (pintype "passive"))
      (node (ref "K73") (pin "P$1") (pinfunction "P$1_P$1") (pintype "bidirectional"))
    )
    (net (code "38") (name "Net-(D80-PadC)") (class "Default")
      (node (ref "D80") (pin "C") (pinfunction "C_C") (pintype "passive"))
      (node (ref "K80") (pin "P$1") (pinfunction "P$1_P$1") (pintype "bidirectional"))
    )
    (net (code "39") (name "Net-(D81-PadC)") (class "Default")
      (node (ref "D81") (pin "C") (pinfunction "C_C") (pintype "passive"))
      (node (ref "K87") (pin "P$1") (pinfunction "P$1_P$1") (pintype "bidirectional"))
    )
    (net (code "40") (name "Net-(D82-PadC)") (class "Default")
      (node (ref "D82") (pin "C") (pinfunction "C_C") (pintype "passive"))
      (node (ref "K93") (pin "P$1") (pinfunction "P$1_P$1") (pintype "bidirectional"))
    )
    (net (code "41") (name "Net-(D83-PadC)") (class "Default")
      (node (ref "D83") (pin "C") (pinfunction "C_C") (pintype "passive"))
      (node (ref "K94") (pin "P$1") (pinfunction "P$1_P$1") (pintype "bidirectional"))
    )
    (net (code "42") (name "Net-(D84-PadC)") (class "Default")
      (node (ref "D84") (pin "C") (pinfunction "C_C") (pintype "passive"))
      (node (ref "K95") (pin "P$1") (pinfunction "P$1_P$1") (pintype "bidirectional"))
    )
    (net (code "43") (name "Net-(D85-PadC)") (class "Default")
      (node (ref "D85") (pin "C") (pinfunction "C_C") (pintype "passive"))
      (node (ref "K96") (pin "P$1") (pinfunction "P$1_P$1") (pintype "bidirectional"))
    )
    (net (code "44") (name "Net-(D86-PadC)") (class "Default")
      (node (ref "D86") (pin "C") (pinfunction "C_C") (pintype "passive"))
      (node (ref "K97") (pin "P$1") (pinfunction "P$1_P$1") (pintype "bidirectional"))
    )
    (net (code "45") (name "Net-(D87-PadC)") (class "Default")
      (node (ref "D87") (pin "C") (pinfunction "C_C") (pintype "passive"))
      (node (ref "K88") (pin "P$1") (pinfunction "P$1_P$1") (pintype "bidirectional"))
    )
    (net (code "46") (name "Net-(D88-PadC)") (class "Default")
      (node (ref "D88") (pin "C") (pinfunction "C_C") (pintype "passive"))
      (node (ref "K81") (pin "P$1") (pinfunction "P$1_P$1") (pintype "bidirectional"))
    )
    (net (code "47") (name "Net-(D89-PadC)") (class "Default")
      (node (ref "D89") (pin "C") (pinfunction "C_C") (pintype "passive"))
      (node (ref "K82") (pin "P$2") (pinfunction "P$2_P$2") (pintype "bidirectional"))
    )
    (net (code "48") (name "Net-(D90-PadC)") (class "Default")
      (node (ref "D90") (pin "C") (pinfunction "C_C") (pintype "passive"))
      (node (ref "K89") (pin "P$1") (pinfunction "P$1_P$1") (pintype "bidirectional"))
    )
    (net (code "49") (name "Net-(D91-PadC)") (class "Default")
      (node (ref "D91") (pin "C") (pinfunction "C_C") (pintype "passive"))
      (node (ref "K83") (pin "P$2") (pinfunction "P$2_P$2") (pintype "bidirectional"))
    )
    (net (code "50") (name "Net-(D92-PadC)") (class "Default")
      (node (ref "D92") (pin "C") (pinfunction "C_C") (pintype "passive"))
      (node (ref "K84") (pin "P$1") (pinfunction "P$1_P$1") (pintype "bidirectional"))
    )
    (net (code "51") (name "Net-(D93-PadC)") (class "Default")
      (node (ref "D93") (pin "C") (pinfunction "C_C") (pintype "passive"))
      (node (ref "K90") (pin "P$1") (pinfunction "P$1_P$1") (pintype "bidirectional"))
    )
    (net (code "52") (name "Net-(D94-PadC)") (class "Default")
      (node (ref "D94") (pin "C") (pinfunction "C_C") (pintype "passive"))
      (node (ref "K91") (pin "P$1") (pinfunction "P$1_P$1") (pintype "bidirectional"))
    )
    (net (code "53") (name "Net-(D95-PadC)") (class "Default")
      (node (ref "D95") (pin "C") (pinfunction "C_C") (pintype "passive"))
      (node (ref "K85") (pin "P$1") (pinfunction "P$1_P$1") (pintype "bidirectional"))
    )
    (net (code "54") (name "Net-(D96-PadC)") (class "Default")
      (node (ref "D96") (pin "C") (pinfunction "C_C") (pintype "passive"))
      (node (ref "K86") (pin "P$1") (pinfunction "P$1_P$1") (pintype "bidirectional"))
    )
    (net (code "55") (name "Net-(D97-PadC)") (class "Default")
      (node (ref "D97") (pin "C") (pinfunction "C_C") (pintype "passive"))
      (node (ref "K92") (pin "P$1") (pinfunction "P$1_P$1") (pintype "bidirectional"))
    )
    (net (code "56") (name "Net-(D98-PadC)") (class "Default")
      (node (ref "D98") (pin "C") (pinfunction "C_C") (pintype "passive"))
      (node (ref "K118") (pin "P$1") (pinfunction "P$1_P$1") (pintype "bidirectional"))
    )
    (net (code "57") (name "Net-(D99-PadC)") (class "Default")
      (node (ref "D99") (pin "C") (pinfunction "C_C") (pintype "passive"))
      (node (ref "K99") (pin "P$1") (pinfunction "P$1_P$1") (pintype "bidirectional"))
    )
    (net (code "58") (name "Net-(D100-PadC)") (class "Default")
      (node (ref "D100") (pin "C") (pinfunction "C_C") (pintype "passive"))
      (node (ref "K100") (pin "P$1") (pinfunction "P$1_P$1") (pintype "bidirectional"))
    )
    (net (code "59") (name "Net-(D101-PadC)") (class "Default")
      (node (ref "D101") (pin "C") (pinfunction "C_C") (pintype "passive"))
      (node (ref "K101") (pin "P$1") (pinfunction "P$1_P$1") (pintype "bidirectional"))
    )
    (net (code "60") (name "Net-(D102-PadC)") (class "Default")
      (node (ref "D102") (pin "C") (pinfunction "C_C") (pintype "passive"))
      (node (ref "K102") (pin "P$1") (pinfunction "P$1_P$1") (pintype "bidirectional"))
    )
    (net (code "61") (name "Net-(D103-PadC)") (class "Default")
      (node (ref "D103") (pin "C") (pinfunction "C_C") (pintype "passive"))
      (node (ref "K103") (pin "P$1") (pinfunction "P$1_P$1") (pintype "bidirectional"))
    )
    (net (code "62") (name "Net-(D104-PadC)") (class "Default")
      (node (ref "D104") (pin "C") (pinfunction "C_C") (pintype "passive"))
      (node (ref "K128") (pin "P$1") (pinfunction "P$1_P$1") (pintype "bidirectional"))
    )
    (net (code "63") (name "Net-(D105-PadC)") (class "Default")
      (node (ref "D105") (pin "C") (pinfunction "C_C") (pintype "passive"))
      (node (ref "K110") (pin "P$1") (pinfunction "P$1_P$1") (pintype "bidirectional"))
    )
    (net (code "64") (name "Net-(D106-PadC)") (class "Default")
      (node (ref "D106") (pin "C") (pinfunction "C_C") (pintype "passive"))
      (node (ref "K109") (pin "P$1") (pinfunction "P$1_P$1") (pintype "bidirectional"))
    )
    (net (code "65") (name "Net-(D107-PadC)") (class "Default")
      (node (ref "D107") (pin "C") (pinfunction "C_C") (pintype "passive"))
      (node (ref "K108") (pin "P$1") (pinfunction "P$1_P$1") (pintype "bidirectional"))
    )
    (net (code "66") (name "Net-(D108-PadC)") (class "Default")
      (node (ref "D108") (pin "C") (pinfunction "C_C") (pintype "passive"))
      (node (ref "K107") (pin "P$1") (pinfunction "P$1_P$1") (pintype "bidirectional"))
    )
    (net (code "67") (name "Net-(D109-PadC)") (class "Default")
      (node (ref "D109") (pin "C") (pinfunction "C_C") (pintype "passive"))
      (node (ref "K106") (pin "P$1") (pinfunction "P$1_P$1") (pintype "bidirectional"))
    )
    (net (code "68") (name "Net-(D110-PadC)") (class "Default")
      (node (ref "D110") (pin "C") (pinfunction "C_C") (pintype "passive"))
      (node (ref "K111") (pin "P$1") (pinfunction "P$1_P$1") (pintype "bidirectional"))
    )
    (net (code "69") (name "Net-(D111-PadC)") (class "Default")
      (node (ref "D111") (pin "C") (pinfunction "C_C") (pintype "passive"))
      (node (ref "K124") (pin "P$1") (pinfunction "P$1_P$1") (pintype "bidirectional"))
    )
    (net (code "70") (name "Net-(D112-PadC)") (class "Default")
      (node (ref "D112") (pin "C") (pinfunction "C_C") (pintype "passive"))
      (node (ref "K125") (pin "P$1") (pinfunction "P$1_P$1") (pintype "bidirectional"))
    )
    (net (code "71") (name "Net-(D113-PadC)") (class "Default")
      (node (ref "D113") (pin "C") (pinfunction "C_C") (pintype "passive"))
      (node (ref "K126") (pin "P$1") (pinfunction "P$1_P$1") (pintype "bidirectional"))
    )
    (net (code "72") (name "Net-(D114-PadC)") (class "Default")
      (node (ref "D114") (pin "C") (pinfunction "C_C") (pintype "passive"))
      (node (ref "K127") (pin "P$1") (pinfunction "P$1_P$1") (pintype "bidirectional"))
    )
    (net (code "73") (name "Net-(D115-PadC)") (class "Default")
      (node (ref "D115") (pin "C") (pinfunction "C_C") (pintype "passive"))
      (node (ref "K104") (pin "P$1") (pinfunction "P$1_P$1") (pintype "bidirectional"))
    )
    (net (code "74") (name "Net-(D116-PadC)") (class "Default")
      (node (ref "D116") (pin "C") (pinfunction "C_C") (pintype "passive"))
      (node (ref "K98") (pin "P$1") (pinfunction "P$1_P$1") (pintype "bidirectional"))
    )
    (net (code "75") (name "Net-(D117-PadC)") (class "Default")
      (node (ref "D117") (pin "C") (pinfunction "C_C") (pintype "passive"))
      (node (ref "K105") (pin "P$1") (pinfunction "P$1_P$1") (pintype "bidirectional"))
    )
    (net (code "76") (name "Net-(D118-PadC)") (class "Default")
      (node (ref "D118") (pin "C") (pinfunction "C_C") (pintype "passive"))
      (node (ref "K112") (pin "P$1") (pinfunction "P$1_P$1") (pintype "bidirectional"))
    )
    (net (code "77") (name "Net-(D119-PadC)") (class "Default")
      (node (ref "D119") (pin "C") (pinfunction "C_C") (pintype "passive"))
      (node (ref "K119") (pin "P$2") (pinfunction "P$2_P$2") (pintype "bidirectional"))
    )
    (net (code "78") (name "Net-(D120-PadC)") (class "Default")
      (node (ref "D120") (pin "C") (pinfunction "C_C") (pintype "passive"))
      (node (ref "K120") (pin "P$1") (pinfunction "P$1_P$1") (pintype "bidirectional"))
    )
    (net (code "79") (name "Net-(D121-PadC)") (class "Default")
      (node (ref "D121") (pin "C") (pinfunction "C_C") (pintype "passive"))
      (node (ref "K113") (pin "P$1") (pinfunction "P$1_P$1") (pintype "bidirectional"))
    )
    (net (code "80") (name "Net-(D122-PadC)") (class "Default")
      (node (ref "D122") (pin "C") (pinfunction "C_C") (pintype "passive"))
      (node (ref "K114") (pin "P$1") (pinfunction "P$1_P$1") (pintype "bidirectional"))
    )
    (net (code "81") (name "Net-(D123-PadC)") (class "Default")
      (node (ref "D123") (pin "C") (pinfunction "C_C") (pintype "passive"))
      (node (ref "K115") (pin "P$1") (pinfunction "P$1_P$1") (pintype "bidirectional"))
    )
    (net (code "82") (name "Net-(D124-PadC)") (class "Default")
      (node (ref "D124") (pin "C") (pinfunction "C_C") (pintype "passive"))
      (node (ref "K116") (pin "P$1") (pinfunction "P$1_P$1") (pintype "bidirectional"))
    )
    (net (code "83") (name "Net-(D125-PadC)") (class "Default")
      (node (ref "D125") (pin "C") (pinfunction "C_C") (pintype "passive"))
      (node (ref "K122") (pin "P$1") (pinfunction "P$1_P$1") (pintype "bidirectional"))
    )
    (net (code "84") (name "Net-(D126-PadC)") (class "Default")
      (node (ref "D126") (pin "C") (pinfunction "C_C") (pintype "passive"))
      (node (ref "K121") (pin "P$1") (pinfunction "P$1_P$1") (pintype "bidirectional"))
    )
    (net (code "85") (name "Net-(D127-PadC)") (class "Default")
      (node (ref "D127") (pin "C") (pinfunction "C_C") (pintype "passive"))
      (node (ref "K123") (pin "P$2") (pinfunction "P$2_P$2") (pintype "bidirectional"))
    )
    (net (code "86") (name "Net-(D128-PadC)") (class "Default")
      (node (ref "D128") (pin "C") (pinfunction "C_C") (pintype "passive"))
      (node (ref "K117") (pin "P$1") (pinfunction "P$1_P$1") (pintype "bidirectional"))
    )
    (net (code "87") (name "Net-(IC1-(PCI18{slash}INT0)PD2)") (class "Default")
      (node (ref "IC1") (pin "4") (pinfunction "(PCI18/INT0)PD2_4") (pintype "bidirectional"))
      (node (ref "R7") (pin "1") (pinfunction "1_1") (pintype "passive"))
    )
    (net (code "88") (name "Net-(IC1-(PCI19{slash}INT1{slash}OC2B)PD3)") (class "Default")
      (node (ref "IC1") (pin "5") (pinfunction "(PCI19/INT1/OC2B)PD3_5") (pintype "bidirectional"))
      (node (ref "R6") (pin "1") (pinfunction "1_1") (pintype "passive"))
    )
    (net (code "89") (name "Net-(IC1-(PCI20{slash}XCK{slash}T0)PD4)") (class "Default")
      (node (ref "IC1") (pin "6") (pinfunction "(PCI20/XCK/T0)PD4_6") (pintype "bidirectional"))
      (node (ref "LED1") (pin "A") (pinfunction "A_A") (pintype "passive"))
    )
    (net (code "90") (name "Net-(IC1-PB6(XTAL1{slash}TOSC1{slash}PCI6))") (class "Default")
      (node (ref "C9") (pin "1") (pinfunction "1_1") (pintype "passive"))
      (node (ref "IC1") (pin "9") (pinfunction "PB6(XTAL1/TOSC1/PCI6)_9") (pintype "bidirectional"))
      (node (ref "Q1") (pin "2") (pinfunction "2_2") (pintype "passive"))
    )
    (net (code "91") (name "Net-(IC1-PB7(XTAL2{slash}TOSC2{slash}PCI7))") (class "Default")
      (node (ref "C10") (pin "1") (pinfunction "1_1") (pintype "passive"))
      (node (ref "IC1") (pin "10") (pinfunction "PB7(XTAL2/TOSC2/PCI7)_10") (pintype "bidirectional"))
      (node (ref "Q1") (pin "1") (pinfunction "1_1") (pintype "passive"))
    )
    (net (code "92") (name "Net-(IC1-PC6({slash}RESET{slash}PCI14))") (class "Default")
      (node (ref "IC1") (pin "1") (pinfunction "PC6(/RESET/PCI14)_1") (pintype "bidirectional"))
      (node (ref "R5") (pin "2") (pinfunction "2_2") (pintype "passive"))
      (node (ref "S1") (pin "1") (pinfunction "S_1") (pintype "passive"))
      (node (ref "S1") (pin "2") (pinfunction "S1_2") (pintype "passive"))
    )
    (net (code "93") (name "Net-(LED1-PadC)") (class "Default")
      (node (ref "LED1") (pin "C") (pinfunction "C_C") (pintype "passive"))
      (node (ref "R3") (pin "1") (pinfunction "1_1") (pintype "passive"))
    )
    (net (code "94") (name "VCC") (class "Default")
      (node (ref "C3") (pin "1") (pinfunction "1_1") (pintype "passive"))
      (node (ref "C4") (pin "1") (pinfunction "1_1") (pintype "passive"))
      (node (ref "C5") (pin "1") (pinfunction "1_1") (pintype "passive"))
      (node (ref "C6") (pin "1") (pinfunction "1_1") (pintype "passive"))
      (node (ref "C7") (pin "1") (pinfunction "1_1") (pintype "passive"))
      (node (ref "IC1") (pin "20") (pinfunction "AVCC_20") (pintype "bidirectional"))
      (node (ref "IC1") (pin "21") (pinfunction "AREF_21") (pintype "bidirectional"))
      (node (ref "IC1") (pin "7") (pinfunction "VCC_7") (pintype "bidirectional"))
      (node (ref "R2") (pin "1") (pinfunction "1_1") (pintype "passive"))
      (node (ref "R5") (pin "1") (pinfunction "1_1") (pintype "passive"))
      (node (ref "U1") (pin "VBUS1") (pinfunction "VBUS_VBUS1") (pintype "bidirectional"))
    )
    (net (code "95") (name "unconnected-(U1-USBID-PadID1)") (class "Default")
      (node (ref "U1") (pin "ID1") (pinfunction "USBID_ID1") (pintype "bidirectional"))
    )
  )
)
